# CANbus.net
KiCad netlist of a schematic drawn in Altium Designer
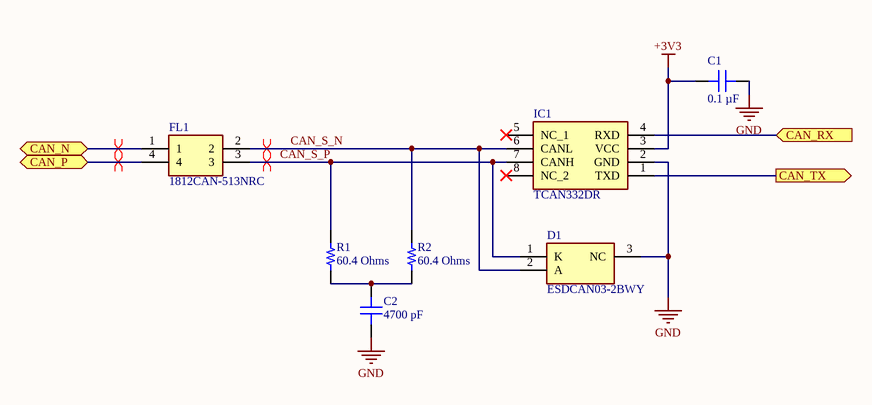
[diagram p0: CANbus.SchDoc]

(export (version "E")
  (design (tool "Eeschema 10.0.6"))
  (components
    (comp (ref "C1")
      (value "0.1 µF")
      (footprint "CAP 0402_1005")
      (description "CAP CER 0402 0.1UF 16V X7R 10%")
      (fields
        (field (name "PART NUMBER") "C0402C104K4RECAUTO")
        (field (name "CAPACITANCE") "0.1 µF")
        (field (name "MANUFACTURER") "KEMET")
      )
      (libsource (lib "Celestial Altium Library - altium_library") (part "Capacitor"))
    )
    (comp (ref "C2")
      (value "4700 pF")
      (footprint "CAP 0402_1005")
      (description "CAP CER 0402 4.7NF 16V X7R 10%")
      (fields
        (field (name "PART NUMBER") "C0402C472K4RECAUTO")
        (field (name "CAPACITANCE") "4700 pF")
        (field (name "MANUFACTURER") "KEMET")
      )
      (libsource (lib "Celestial Altium Library - altium_library") (part "Capacitor"))
    )
    (comp (ref "D1")
      (value "ESDCAN03-2BWY")
      (footprint "PcbLib1:SOT65P210X110-3N")
      (description "TVS Diode (Uni-directional)")
      (fields (field (name "MOUSER PART NUMBER") "511-ESDCAN03-2BWY"))
      (libsource (lib "*") (part "ESDCAN03-2BWY"))
    )
    (comp (ref "FL1")
      (value "1812CAN-513NRC")
      (footprint "PcbLib1:1812CAN513NRC")
      (description "Filter")
      (fields (field (name "MOUSER PART NUMBER") "994-1812CAN-513NRC"))
      (libsource (lib "*") (part "1812CAN-513NRC"))
    )
    (comp (ref "IC1")
      (value "TCAN332DR")
      (footprint "PcbLib1:SOIC127P600X175-8N")
      (description "Integrated Circuit")
      (fields (field (name "MOUSER PART NUMBER") "595-TCAN332DR"))
      (libsource (lib "*") (part "TCAN332DR"))
    )
    (comp (ref "R1")
      (value "60.4 Ohms")
      (footprint "RES 0402_1005")
      (description "RES SMD 60.4 OHM 1% 1/16W 0402")
      (fields (field (name "PART NUMBER") "CRCW040260R4FKED") (field (name "MANUFACTURER") "Vishay Dale"))
      (libsource (lib "Celestial Altium Library - altium_library") (part "Resistor"))
    )
    (comp (ref "R2")
      (value "60.4 Ohms")
      (footprint "RES 0402_1005")
      (description "RES SMD 60.4 OHM 1% 1/16W 0402")
      (fields (field (name "PART NUMBER") "CRCW040260R4FKED") (field (name "MANUFACTURER") "Vishay Dale"))
      (libsource (lib "Celestial Altium Library - altium_library") (part "Resistor"))
    )
  )
  (nets
    (net (code "1") (name "+3V3") (class "Default")
      (node (ref "C1") (pin "1") (pinfunction "1_1") (pintype "passive"))
      (node (ref "IC1") (pin "3") (pinfunction "VCC_3") (pintype "passive"))
    )
    (net (code "2") (name "/CAN_N") (class "Default")
      (node (ref "FL1") (pin "1") (pinfunction "1_1") (pintype "passive"))
    )
    (net (code "3") (name "/CAN_P") (class "Default")
      (node (ref "FL1") (pin "4") (pinfunction "4_4") (pintype "passive"))
    )
    (net (code "4") (name "/CAN_RX") (class "Default")
      (node (ref "IC1") (pin "4") (pinfunction "RXD_4") (pintype "passive"))
    )
    (net (code "5") (name "/CAN_S_N") (class "Default")
      (node (ref "D1") (pin "2") (pinfunction "A_2") (pintype "passive"))
      (node (ref "FL1") (pin "2") (pinfunction "2_2") (pintype "passive"))
      (node (ref "IC1") (pin "6") (pinfunction "CANL_6") (pintype "passive"))
      (node (ref "R2") (pin "1") (pinfunction "1_1") (pintype "passive"))
    )
    (net (code "6") (name "/CAN_S_P") (class "Default")
      (node (ref "D1") (pin "1") (pinfunction "K_1") (pintype "passive"))
      (node (ref "FL1") (pin "3") (pinfunction "3_3") (pintype "passive"))
      (node (ref "IC1") (pin "7") (pinfunction "CANH_7") (pintype "passive"))
      (node (ref "R1") (pin "1") (pinfunction "1_1") (pintype "passive"))
    )
    (net (code "7") (name "/CAN_TX") (class "Default")
      (node (ref "IC1") (pin "1") (pinfunction "TXD_1") (pintype "passive"))
    )
    (net (code "8") (name "GND") (class "Default")
      (node (ref "C1") (pin "2") (pinfunction "2_2") (pintype "passive"))
      (node (ref "C2") (pin "1") (pinfunction "1_1") (pintype "passive"))
      (node (ref "D1") (pin "3") (pinfunction "NC_3") (pintype "passive"))
      (node (ref "IC1") (pin "2") (pinfunction "GND_2") (pintype "passive"))
    )
    (net (code "9") (name "Net-(C2-Pad2)") (class "Default")
      (node (ref "C2") (pin "2") (pinfunction "2_2") (pintype "passive"))
      (node (ref "R1") (pin "2") (pinfunction "2_2") (pintype "passive"))
      (node (ref "R2") (pin "2") (pinfunction "2_2") (pintype "passive"))
    )
    (net (code "10") (name "unconnected-(IC1-NC_1-Pad5)") (class "Default")
      (node (ref "IC1") (pin "5") (pinfunction "NC_1_5") (pintype "passive+no_connect"))
    )
    (net (code "11") (name "unconnected-(IC1-NC_2-Pad8)") (class "Default")
      (node (ref "IC1") (pin "8") (pinfunction "NC_2_8") (pintype "passive+no_connect"))
    )
  )
)
